# efr32_lcd_hmi.net
KiCad netlist of a schematic drawn in Altium Designer
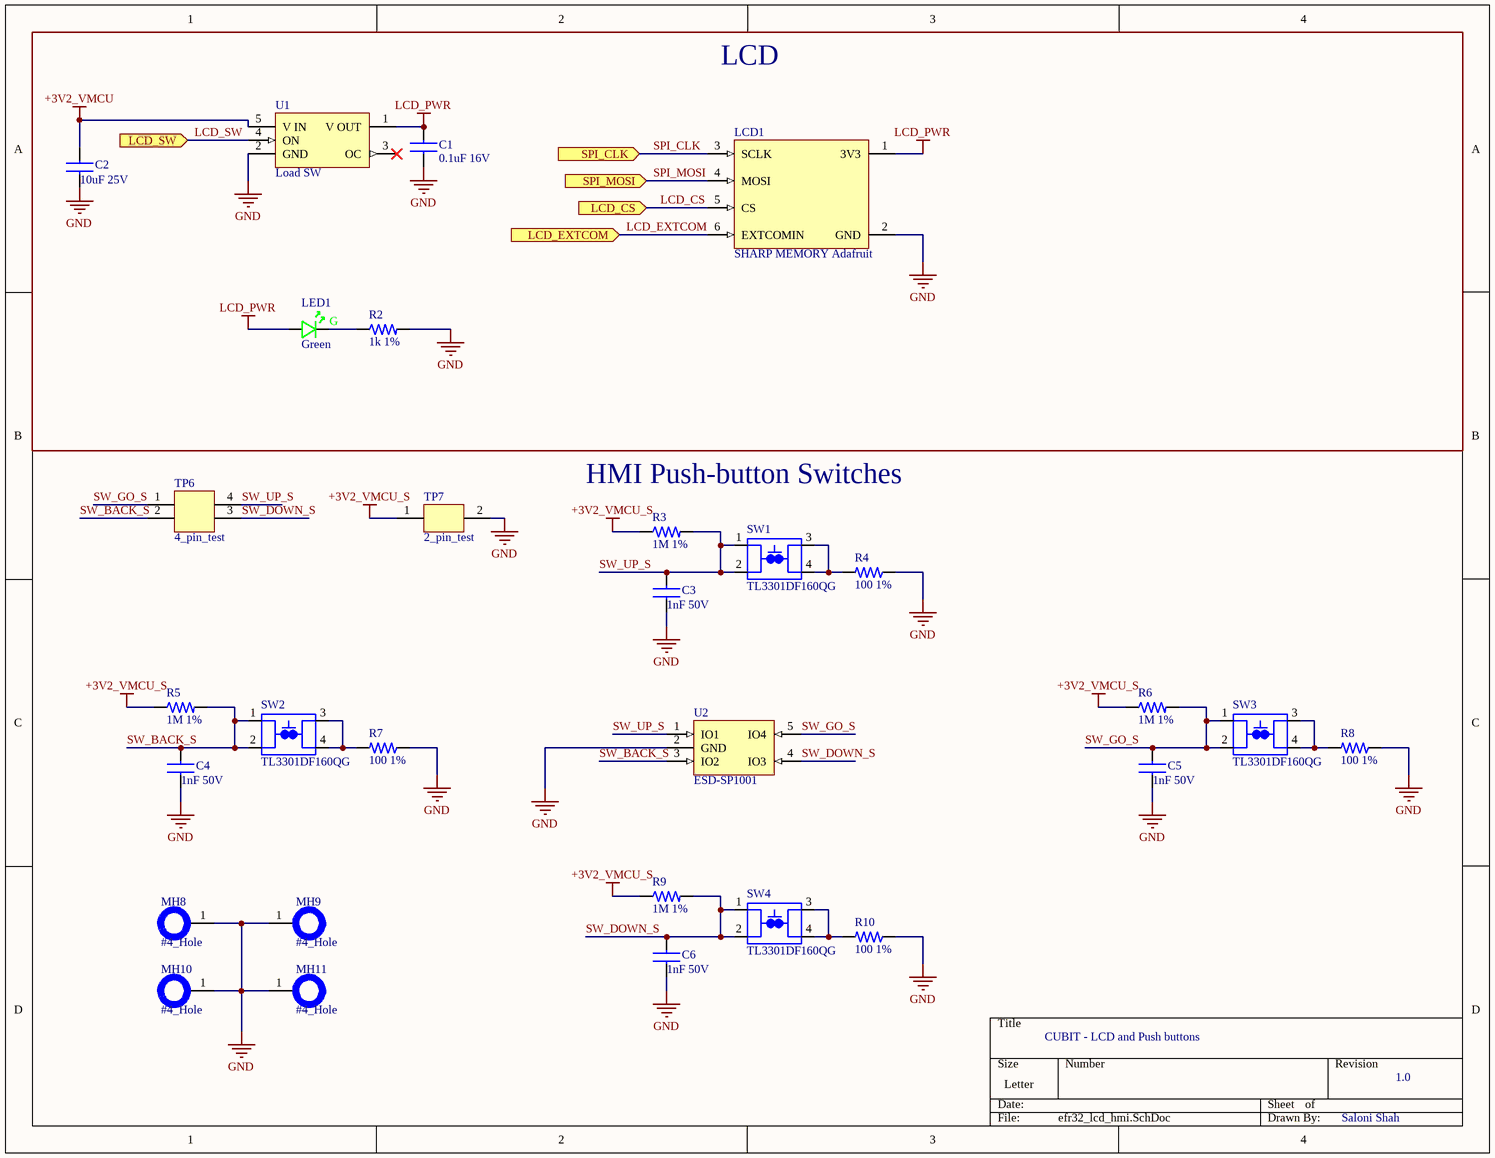
[diagram p0: efr32_lcd_hmi.SchDoc]

(export (version "E")
  (design (tool "Eeschema 10.0.6"))
  (components
    (comp (ref "C1")
      (value "0.1uF 16V")
      (footprint "CAP_0603_1MM")
      (description "Cap Ceramic 0.1uF 16V X7R 10% SMD 0603 125°C Paper T/R")
      (fields
        (field (name "MANUFACTURER") "KEMET")
        (field (name "MANUFACTURER PART NUMBER") "C0805C104K4RACAUTO")
      )
      (libsource (lib "LPEDT_proj_lib") (part "C0805C104K4RACAUTO"))
    )
    (comp (ref "C2")
      (value "10uF 25V")
      (footprint "LPEDT_proj_lib:CAP_0805_02X125")
      (description "Cap 0805 25 V 10 uF ±20% Tolerance X5R Monolithic Ceramic Chip Capacitor")
      (fields
        (field (name "MANUFACTURER") "Murata")
        (field (name "MANUFACTURER PART NUMBER") "GRM21BR61E106KA73K")
      )
      (libsource (lib "LPEDT_proj_lib") (part "GRM21BR61E106KA73K"))
    )
    (comp (ref "C3")
      (value "1nF 50V")
      (footprint "LPEDT_proj_lib:CAP_0805_02X125")
      (description "1nF ±10% 50V X7R 0805")
      (fields
        (field (name "MANUFACTURER") "Samsung")
        (field (name "MANUFACTURER PART NUMBER") "CL21B102KBANFNC")
      )
      (libsource (lib "LPEDT_proj_lib") (part "CL21B102KBANFNC"))
    )
    (comp (ref "C4")
      (value "1nF 50V")
      (footprint "LPEDT_proj_lib:CAP_0805_02X125")
      (description "1nF ±10% 50V X7R 0805")
      (fields
        (field (name "MANUFACTURER") "Samsung")
        (field (name "MANUFACTURER PART NUMBER") "CL21B102KBANFNC")
      )
      (libsource (lib "LPEDT_proj_lib") (part "CL21B102KBANFNC"))
    )
    (comp (ref "C5")
      (value "1nF 50V")
      (footprint "LPEDT_proj_lib:CAP_0805_02X125")
      (description "1nF ±10% 50V X7R 0805")
      (fields
        (field (name "MANUFACTURER") "Samsung")
        (field (name "MANUFACTURER PART NUMBER") "CL21B102KBANFNC")
      )
      (libsource (lib "LPEDT_proj_lib") (part "CL21B102KBANFNC"))
    )
    (comp (ref "C6")
      (value "1nF 50V")
      (footprint "LPEDT_proj_lib:CAP_0805_02X125")
      (description "1nF ±10% 50V X7R 0805")
      (fields
        (field (name "MANUFACTURER") "Samsung")
        (field (name "MANUFACTURER PART NUMBER") "CL21B102KBANFNC")
      )
      (libsource (lib "LPEDT_proj_lib") (part "CL21B102KBANFNC"))
    )
    (comp (ref "LCD1")
      (value "SHARP MEMORY Adafruit")
      (footprint "6_PIN_100MIL")
      (description "Conn AV RCA (Phono) Plug 2 Cont Sz 0.125\" Cbl Mnt Clamp Copper Alloy")
      (fields
        (field (name "MANUFACTURER") "Adafruit Industries")
        (field (name "MANUFACTURER PART NUMBER") "3502")
      )
      (libsource (lib "LPEDT_proj_lib") (part "3502"))
    )
    (comp (ref "LED1")
      (value "Green")
      (footprint "LED_0603_RED_WL-SMCW")
      (description "Led Green Clear 0603 SMD")
      (fields
        (field (name "MANUFACTURER") "QT-Brightek")
        (field (name "MANUFACTURER PART NUMBER") "QBLP601-AG1")
      )
      (libsource (lib "LPEDT_proj_lib") (part "QBLP601-AG1"))
    )
    (comp (ref "MH8")
      (value "#4_Hole")
      (footprint "LPEDT_proj_lib:HOLE_#4")
      (libsource (lib "LPEDT_proj_lib") (part "Mechanical_Hole"))
    )
    (comp (ref "MH9")
      (value "#4_Hole")
      (footprint "LPEDT_proj_lib:HOLE_#4")
      (libsource (lib "LPEDT_proj_lib") (part "Mechanical_Hole"))
    )
    (comp (ref "MH10")
      (value "#4_Hole")
      (footprint "LPEDT_proj_lib:HOLE_#4")
      (libsource (lib "LPEDT_proj_lib") (part "Mechanical_Hole"))
    )
    (comp (ref "MH11")
      (value "#4_Hole")
      (footprint "LPEDT_proj_lib:HOLE_#4")
      (libsource (lib "LPEDT_proj_lib") (part "Mechanical_Hole"))
    )
    (comp (ref "R2")
      (value "1k 1%")
      (footprint "2_Chip_0603_RMCF")
      (description "Res 1K Ohm 1% 0.1W(1/10W) ±100ppm/C Pad SMD Automotive T/R")
      (fields
        (field (name "MANUFACTURER") "Stackpole Electronics")
        (field (name "MANUFACTURER PART NUMBER") "RMCF0603FT1K00")
      )
      (libsource (lib "LPEDT_proj_lib") (part "RMCF0603FT1K00"))
    )
    (comp (ref "R3")
      (value "1M 1%")
      (footprint "2_Chip_0603_RMCF")
      (description "Res 1M Ohm 1% 1/10W ±100ppm/°C Molded SMD Paper T/R")
      (fields
        (field (name "MANUFACTURER") "Stackpole Electronics")
        (field (name "MANUFACTURER PART NUMBER") "RMCF0603FT1M00")
      )
      (libsource (lib "LPEDT_proj_lib") (part "RMCF0603FT1M00"))
    )
    (comp (ref "R4")
      (value "100 1%")
      (footprint "2_Chip_0603_RMCF")
      (description "Res 100 Ohm 1% 1/10W ±100ppm/°C Molded SMD SMD Paper T/R")
      (fields
        (field (name "MANUFACTURER") "Stackpole Electronics")
        (field (name "MANUFACTURER PART NUMBER") "RMCF0603FT100R")
      )
      (libsource (lib "LPEDT_proj_lib") (part "RMCF0603FT100R"))
    )
    (comp (ref "R5")
      (value "1M 1%")
      (footprint "2_Chip_0603_RMCF")
      (description "Res 1M Ohm 1% 1/10W ±100ppm/°C Molded SMD Paper T/R")
      (fields
        (field (name "MANUFACTURER") "Stackpole Electronics")
        (field (name "MANUFACTURER PART NUMBER") "RMCF0603FT1M00")
      )
      (libsource (lib "LPEDT_proj_lib") (part "RMCF0603FT1M00"))
    )
    (comp (ref "R6")
      (value "1M 1%")
      (footprint "2_Chip_0603_RMCF")
      (description "Res 1M Ohm 1% 1/10W ±100ppm/°C Molded SMD Paper T/R")
      (fields
        (field (name "MANUFACTURER") "Stackpole Electronics")
        (field (name "MANUFACTURER PART NUMBER") "RMCF0603FT1M00")
      )
      (libsource (lib "LPEDT_proj_lib") (part "RMCF0603FT1M00"))
    )
    (comp (ref "R7")
      (value "100 1%")
      (footprint "2_Chip_0603_RMCF")
      (description "Res 100 Ohm 1% 1/10W ±100ppm/°C Molded SMD SMD Paper T/R")
      (fields
        (field (name "MANUFACTURER") "Stackpole Electronics")
        (field (name "MANUFACTURER PART NUMBER") "RMCF0603FT100R")
      )
      (libsource (lib "LPEDT_proj_lib") (part "RMCF0603FT100R"))
    )
    (comp (ref "R8")
      (value "100 1%")
      (footprint "2_Chip_0603_RMCF")
      (description "Res 100 Ohm 1% 1/10W ±100ppm/°C Molded SMD SMD Paper T/R")
      (fields
        (field (name "MANUFACTURER") "Stackpole Electronics")
        (field (name "MANUFACTURER PART NUMBER") "RMCF0603FT100R")
      )
      (libsource (lib "LPEDT_proj_lib") (part "RMCF0603FT100R"))
    )
    (comp (ref "R9")
      (value "1M 1%")
      (footprint "2_Chip_0603_RMCF")
      (description "Res 1M Ohm 1% 1/10W ±100ppm/°C Molded SMD Paper T/R")
      (fields
        (field (name "MANUFACTURER") "Stackpole Electronics")
        (field (name "MANUFACTURER PART NUMBER") "RMCF0603FT1M00")
      )
      (libsource (lib "LPEDT_proj_lib") (part "RMCF0603FT1M00"))
    )
    (comp (ref "R10")
      (value "100 1%")
      (footprint "2_Chip_0603_RMCF")
      (description "Res 100 Ohm 1% 1/10W ±100ppm/°C Molded SMD SMD Paper T/R")
      (fields
        (field (name "MANUFACTURER") "Stackpole Electronics")
        (field (name "MANUFACTURER PART NUMBER") "RMCF0603FT100R")
      )
      (libsource (lib "LPEDT_proj_lib") (part "RMCF0603FT100R"))
    )
    (comp (ref "SW1")
      (value "TL3301DF160QG")
      (footprint "SW_TL3301DF160QG")
      (description "Tactile Switch SPST-NO Top Actuated Surface Mount")
      (fields (field (name "MF") "E-Switch"))
      (libsource (lib "LPEDT_proj_lib") (part "TL3301DF160QG"))
    )
    (comp (ref "SW2")
      (value "TL3301DF160QG")
      (footprint "SW_TL3301DF160QG")
      (description "Tactile Switch SPST-NO Top Actuated Surface Mount")
      (fields (field (name "MF") "E-Switch"))
      (libsource (lib "LPEDT_proj_lib") (part "TL3301DF160QG"))
    )
    (comp (ref "SW3")
      (value "TL3301DF160QG")
      (footprint "SW_TL3301DF160QG")
      (description "Tactile Switch SPST-NO Top Actuated Surface Mount")
      (fields (field (name "MF") "E-Switch"))
      (libsource (lib "LPEDT_proj_lib") (part "TL3301DF160QG"))
    )
    (comp (ref "SW4")
      (value "TL3301DF160QG")
      (footprint "SW_TL3301DF160QG")
      (description "Tactile Switch SPST-NO Top Actuated Surface Mount")
      (fields (field (name "MF") "E-Switch"))
      (libsource (lib "LPEDT_proj_lib") (part "TL3301DF160QG"))
    )
    (comp (ref "TP6")
      (value "4_pin_test")
      (footprint "4_PIN_100MIL")
      (libsource (lib "LPEDT_proj_lib") (part "4_pin_test"))
    )
    (comp (ref "TP7")
      (value "2_pin_test")
      (footprint "2_PIN_100mil")
      (libsource (lib "LPEDT_proj_lib") (part "2_pin_test"))
    )
    (comp (ref "U1")
      (value "Load SW")
      (footprint "SOT65P210X110-5N")
      (description "5.5-V, 0.1-A, 500-mΩ, load switch with current limit and active low enable 5-SC70 -40 to 85")
      (fields
        (field (name "MANUFACTURER") "Texas Instruments")
        (field (name "MANUFACTURER PART NUMBER") "TPS22942DCKR")
      )
      (libsource (lib "LPEDT_proj_lib") (part "TPS22942DCKR"))
    )
    (comp (ref "U2")
      (value "ESD-SP1001")
      (footprint "SOT65P210X110-5N")
      (description "TVS DIODE 5.5VWM 13VC SC70-5")
      (fields
        (field (name "MANUFACTURER") "Littelfuse")
        (field (name "MANUFACTURER PART NUMBER") "SP1001-04JTG")
      )
      (libsource (lib "LPEDT_proj_lib") (part "SP1001-04JTG"))
    )
  )
  (nets
    (net (code "1") (name "+3V2_VMCU") (class "Default")
      (node (ref "C2") (pin "1") (pinfunction "1_1") (pintype "passive"))
      (node (ref "U1") (pin "5") (pinfunction "V_IN_5") (pintype "power_in"))
    )
    (net (code "2") (name "+3V2_VMCU_S") (class "Default")
      (node (ref "R3") (pin "1") (pinfunction "1_1") (pintype "passive"))
      (node (ref "R5") (pin "1") (pinfunction "1_1") (pintype "passive"))
      (node (ref "R6") (pin "1") (pinfunction "1_1") (pintype "passive"))
      (node (ref "R9") (pin "1") (pinfunction "1_1") (pintype "passive"))
      (node (ref "TP7") (pin "1") (pintype "passive"))
    )
    (net (code "3") (name "/LCD_CS") (class "Default")
      (node (ref "LCD1") (pin "5") (pinfunction "CS_5") (pintype "input"))
    )
    (net (code "4") (name "/LCD_EXTCOM") (class "Default")
      (node (ref "LCD1") (pin "6") (pinfunction "EXTCOMIN_6") (pintype "input"))
    )
    (net (code "5") (name "/LCD_SW") (class "Default")
      (node (ref "U1") (pin "4") (pinfunction "ON_4") (pintype "input"))
    )
    (net (code "6") (name "/SPI_CLK") (class "Default")
      (node (ref "LCD1") (pin "3") (pinfunction "SCLK_3") (pintype "input"))
    )
    (net (code "7") (name "/SPI_MOSI") (class "Default")
      (node (ref "LCD1") (pin "4") (pinfunction "MOSI_4") (pintype "input"))
    )
    (net (code "8") (name "/SW_BACK_S") (class "Default")
      (node (ref "C4") (pin "1") (pinfunction "1_1") (pintype "passive"))
      (node (ref "R5") (pin "2") (pinfunction "2_2") (pintype "passive"))
      (node (ref "SW2") (pin "1") (pinfunction "1_1") (pintype "passive"))
      (node (ref "SW2") (pin "2") (pinfunction "2_2") (pintype "passive"))
      (node (ref "TP6") (pin "2") (pintype "passive"))
      (node (ref "U2") (pin "3") (pinfunction "IO2_3") (pintype "input"))
    )
    (net (code "9") (name "/SW_DOWN_S") (class "Default")
      (node (ref "C6") (pin "1") (pinfunction "1_1") (pintype "passive"))
      (node (ref "R9") (pin "2") (pinfunction "2_2") (pintype "passive"))
      (node (ref "SW4") (pin "1") (pinfunction "1_1") (pintype "passive"))
      (node (ref "SW4") (pin "2") (pinfunction "2_2") (pintype "passive"))
      (node (ref "TP6") (pin "3") (pintype "passive"))
      (node (ref "U2") (pin "4") (pinfunction "IO3_4") (pintype "input"))
    )
    (net (code "10") (name "/SW_GO_S") (class "Default")
      (node (ref "C5") (pin "1") (pinfunction "1_1") (pintype "passive"))
      (node (ref "R6") (pin "2") (pinfunction "2_2") (pintype "passive"))
      (node (ref "SW3") (pin "1") (pinfunction "1_1") (pintype "passive"))
      (node (ref "SW3") (pin "2") (pinfunction "2_2") (pintype "passive"))
      (node (ref "TP6") (pin "1") (pintype "passive"))
      (node (ref "U2") (pin "5") (pinfunction "IO4_5") (pintype "input"))
    )
    (net (code "11") (name "/SW_UP_S") (class "Default")
      (node (ref "C3") (pin "1") (pinfunction "1_1") (pintype "passive"))
      (node (ref "R3") (pin "2") (pinfunction "2_2") (pintype "passive"))
      (node (ref "SW1") (pin "1") (pinfunction "1_1") (pintype "passive"))
      (node (ref "SW1") (pin "2") (pinfunction "2_2") (pintype "passive"))
      (node (ref "TP6") (pin "4") (pintype "passive"))
      (node (ref "U2") (pin "1") (pinfunction "IO1_1") (pintype "input"))
    )
    (net (code "12") (name "GND") (class "Default")
      (node (ref "C1") (pin "2") (pinfunction "2_2") (pintype "passive"))
      (node (ref "C2") (pin "2") (pinfunction "2_2") (pintype "passive"))
      (node (ref "C3") (pin "2") (pinfunction "2_2") (pintype "passive"))
      (node (ref "C4") (pin "2") (pinfunction "2_2") (pintype "passive"))
      (node (ref "C5") (pin "2") (pinfunction "2_2") (pintype "passive"))
      (node (ref "C6") (pin "2") (pinfunction "2_2") (pintype "passive"))
      (node (ref "LCD1") (pin "2") (pinfunction "GND_2") (pintype "power_in"))
      (node (ref "MH10") (pin "1") (pinfunction "1_1") (pintype "passive"))
      (node (ref "MH11") (pin "1") (pinfunction "1_1") (pintype "passive"))
      (node (ref "MH8") (pin "1") (pinfunction "1_1") (pintype "passive"))
      (node (ref "MH9") (pin "1") (pinfunction "1_1") (pintype "passive"))
      (node (ref "R10") (pin "1") (pinfunction "1_1") (pintype "passive"))
      (node (ref "R2") (pin "2") (pinfunction "2_2") (pintype "passive"))
      (node (ref "R4") (pin "1") (pinfunction "1_1") (pintype "passive"))
      (node (ref "R7") (pin "1") (pinfunction "1_1") (pintype "passive"))
      (node (ref "R8") (pin "1") (pinfunction "1_1") (pintype "passive"))
      (node (ref "TP7") (pin "2") (pintype "passive"))
      (node (ref "U1") (pin "2") (pinfunction "GND_2") (pintype "power_in"))
      (node (ref "U2") (pin "2") (pinfunction "GND_2") (pintype "power_in"))
    )
    (net (code "13") (name "LCD_PWR") (class "Default")
      (node (ref "C1") (pin "1") (pinfunction "1_1") (pintype "passive"))
      (node (ref "LCD1") (pin "1") (pinfunction "3V3_1") (pintype "power_in"))
      (node (ref "LED1") (pin "A") (pinfunction "A_A") (pintype "passive"))
      (node (ref "U1") (pin "1") (pinfunction "V_OUT_1") (pintype "power_in"))
    )
    (net (code "14") (name "Net-(LED1-PadC)") (class "Default")
      (node (ref "LED1") (pin "C") (pinfunction "C_C") (pintype "passive"))
      (node (ref "R2") (pin "1") (pinfunction "1_1") (pintype "passive"))
    )
    (net (code "15") (name "Net-(R4-Pad2)") (class "Default")
      (node (ref "R4") (pin "2") (pinfunction "2_2") (pintype "passive"))
      (node (ref "SW1") (pin "3") (pinfunction "3_3") (pintype "passive"))
      (node (ref "SW1") (pin "4") (pinfunction "4_4") (pintype "passive"))
    )
    (net (code "16") (name "Net-(R7-Pad2)") (class "Default")
      (node (ref "R7") (pin "2") (pinfunction "2_2") (pintype "passive"))
      (node (ref "SW2") (pin "3") (pinfunction "3_3") (pintype "passive"))
      (node (ref "SW2") (pin "4") (pinfunction "4_4") (pintype "passive"))
    )
    (net (code "17") (name "Net-(R8-Pad2)") (class "Default")
      (node (ref "R8") (pin "2") (pinfunction "2_2") (pintype "passive"))
      (node (ref "SW3") (pin "3") (pinfunction "3_3") (pintype "passive"))
      (node (ref "SW3") (pin "4") (pinfunction "4_4") (pintype "passive"))
    )
    (net (code "18") (name "Net-(R10-Pad2)") (class "Default")
      (node (ref "R10") (pin "2") (pinfunction "2_2") (pintype "passive"))
      (node (ref "SW4") (pin "3") (pinfunction "3_3") (pintype "passive"))
      (node (ref "SW4") (pin "4") (pinfunction "4_4") (pintype "passive"))
    )
    (net (code "19") (name "unconnected-(U1-OC-Pad3)") (class "Default")
      (node (ref "U1") (pin "3") (pinfunction "OC_3") (pintype "output+no_connect"))
    )
  )
)
